# PS-VCO.net
KiCad netlist of a schematic drawn in EAGLE
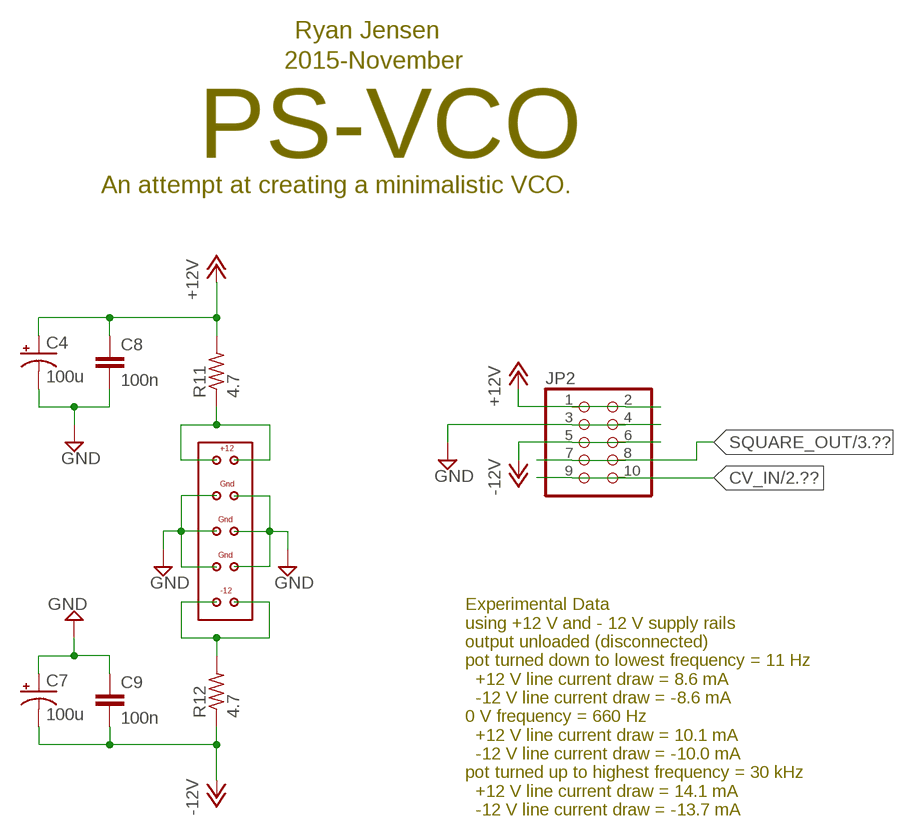
[diagram p0: schematic, sheet 1]
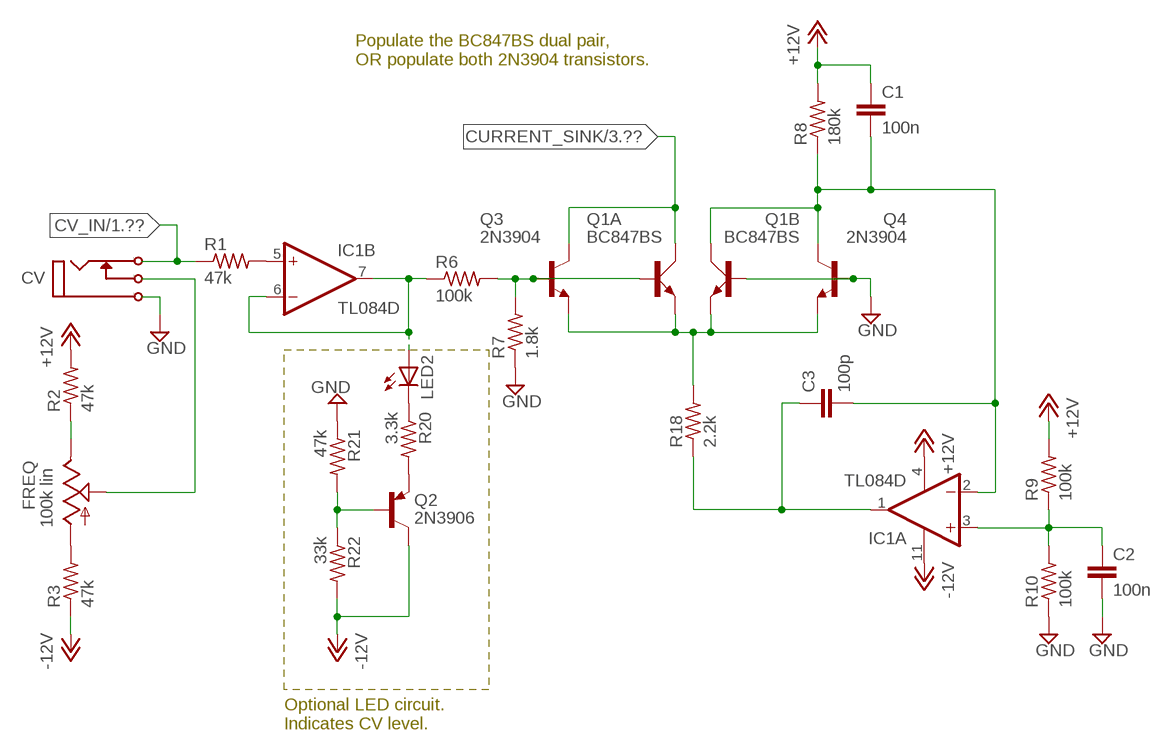
[diagram p1: schematic, sheet 2]
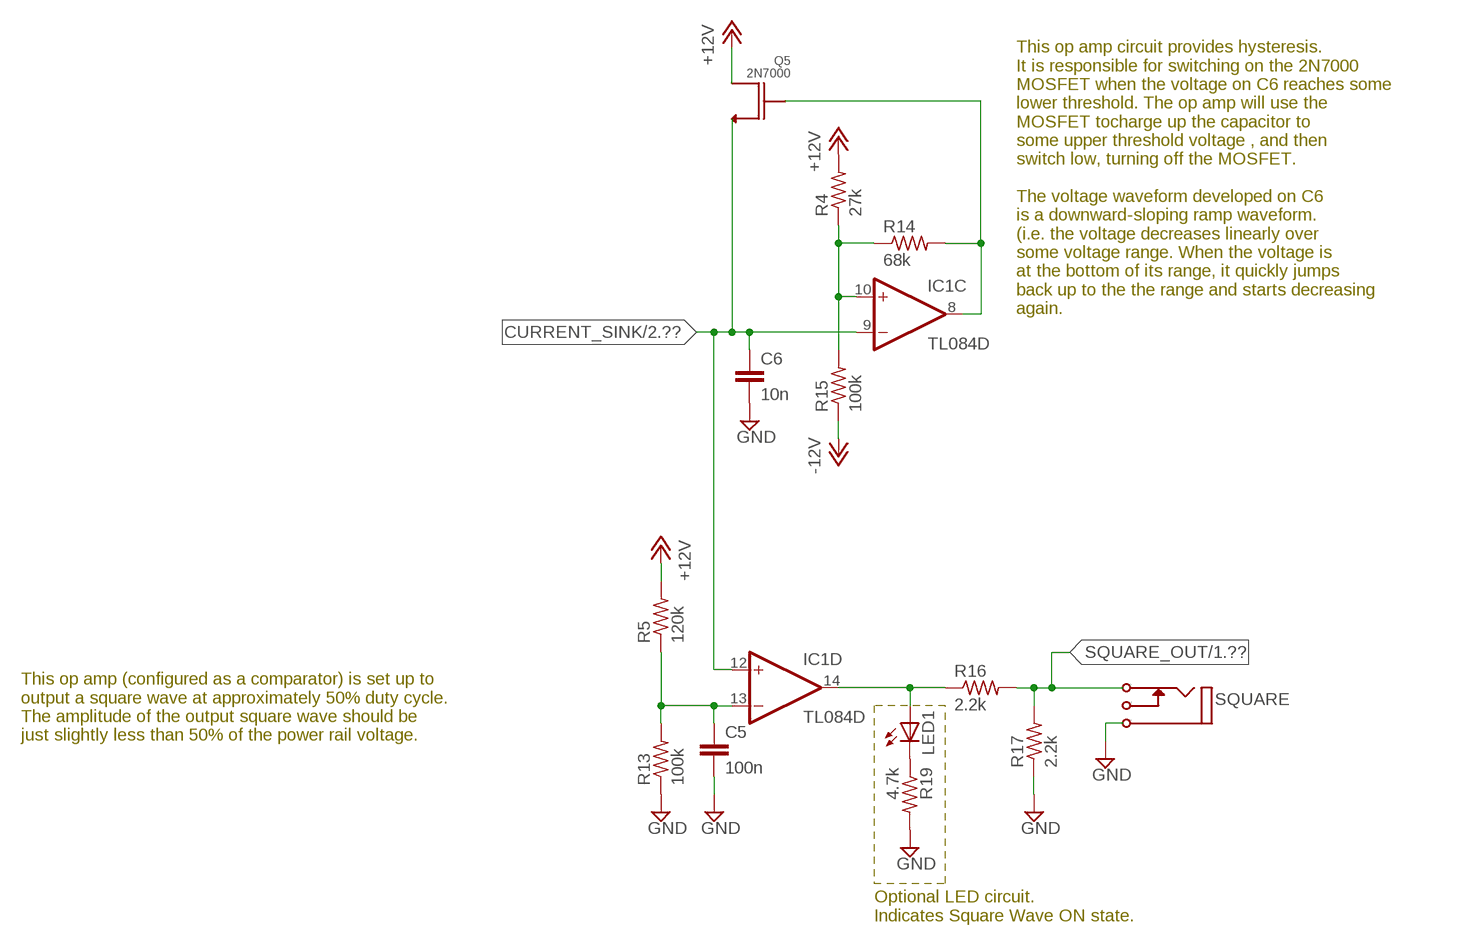
[diagram p2: schematic, sheet 3]

(export (version "E")
  (design (tool "Eeschema 10.0.6"))
  (components
    (comp (ref "C1")
      (value "100n")
      (footprint "eagle-import:C0603")
      (libsource (lib "eagle-import") (part "C-EUC0603"))
    )
    (comp (ref "C2")
      (value "100n")
      (footprint "eagle-import:C0603")
      (libsource (lib "eagle-import") (part "C-EUC0603"))
    )
    (comp (ref "C3")
      (value "100p")
      (footprint "eagle-import:C0603")
      (libsource (lib "eagle-import") (part "C-EUC0603"))
    )
    (comp (ref "CV")
      (value "CV")
      (footprint "eagle-import:MONO_JACK")
      (libsource (lib "eagle-import") (part "MONO_JACK"))
    )
    (comp (ref "FREQ")
      (value "100k lin")
      (footprint "eagle-import:B64Y")
      (libsource (lib "eagle-import") (part "TRIM_US-B64Y"))
    )
    (comp (ref "IC1")
      (value "TL084D")
      (footprint "eagle-import:SO14")
      (libsource (lib "eagle-import") (part "TL084D"))
    )
    (comp (ref "LED2")
      (value "LED_ELD260")
      (footprint "eagle-import:LED_LD260")
      (libsource (lib "eagle-import") (part "LED_ELD260"))
    )
    (comp (ref "Q1")
      (value "BC847BS")
      (footprint "eagle-import:SOT363_PHILIPS")
      (libsource (lib "eagle-import") (part "BC847BS"))
    )
    (comp (ref "Q2")
      (value "2N3906")
      (footprint "eagle-import:TO92")
      (libsource (lib "eagle-import") (part "2N3906"))
    )
    (comp (ref "Q3")
      (value "2N3904")
      (footprint "eagle-import:TO92")
      (libsource (lib "eagle-import") (part "2N3904"))
    )
    (comp (ref "Q4")
      (value "2N3904")
      (footprint "eagle-import:TO92")
      (libsource (lib "eagle-import") (part "2N3904"))
    )
    (comp (ref "R1")
      (value "47k")
      (footprint "eagle-import:R0603")
      (libsource (lib "eagle-import") (part "R-US_R0603"))
    )
    (comp (ref "R2")
      (value "47k")
      (footprint "eagle-import:R0603")
      (libsource (lib "eagle-import") (part "R-US_R0603"))
    )
    (comp (ref "R3")
      (value "47k")
      (footprint "eagle-import:R0603")
      (libsource (lib "eagle-import") (part "R-US_R0603"))
    )
    (comp (ref "R6")
      (value "100k")
      (footprint "eagle-import:R0603")
      (libsource (lib "eagle-import") (part "R-US_R0603"))
    )
    (comp (ref "R7")
      (value "1.8k")
      (footprint "eagle-import:R0603")
      (libsource (lib "eagle-import") (part "R-US_R0603"))
    )
    (comp (ref "R8")
      (value "180k")
      (footprint "eagle-import:R0603")
      (libsource (lib "eagle-import") (part "R-US_R0603"))
    )
    (comp (ref "R9")
      (value "100k")
      (footprint "eagle-import:R0603")
      (libsource (lib "eagle-import") (part "R-US_R0603"))
    )
    (comp (ref "R10")
      (value "100k")
      (footprint "eagle-import:R0603")
      (libsource (lib "eagle-import") (part "R-US_R0603"))
    )
    (comp (ref "R18")
      (value "2.2k")
      (footprint "eagle-import:R0603")
      (libsource (lib "eagle-import") (part "R-US_R0603"))
    )
    (comp (ref "R20")
      (value "3.3k")
      (footprint "eagle-import:R0603")
      (libsource (lib "eagle-import") (part "R-US_R0603"))
    )
    (comp (ref "R21")
      (value "47k")
      (footprint "eagle-import:R0603")
      (libsource (lib "eagle-import") (part "R-US_R0603"))
    )
    (comp (ref "R22")
      (value "33k")
      (footprint "eagle-import:R0603")
      (libsource (lib "eagle-import") (part "R-US_R0603"))
    )
    (comp (ref "C4")
      (value "100u")
      (footprint "eagle-import:E2,5-7")
      (libsource (lib "eagle-import") (part "CPOL-USE2.5-7"))
    )
    (comp (ref "C7")
      (value "100u")
      (footprint "eagle-import:E2,5-7")
      (libsource (lib "eagle-import") (part "CPOL-USE2.5-7"))
    )
    (comp (ref "C8")
      (value "100n")
      (footprint "eagle-import:C0603")
      (libsource (lib "eagle-import") (part "C-EUC0603"))
    )
    (comp (ref "C9")
      (value "100n")
      (footprint "eagle-import:C0603")
      (libsource (lib "eagle-import") (part "C-EUC0603"))
    )
    (comp (ref "JP2")
      (value "PINHD-2X5")
      (footprint "eagle-import:2X05")
      (libsource (lib "eagle-import") (part "PINHD-2X5"))
    )
    (comp (ref "R11")
      (value "4.7")
      (footprint "eagle-import:R0603")
      (libsource (lib "eagle-import") (part "R-US_R0603"))
    )
    (comp (ref "R12")
      (value "4.7")
      (footprint "eagle-import:R0603")
      (libsource (lib "eagle-import") (part "R-US_R0603"))
    )
    (comp (ref "U$3")
      (value "EURORACK-POWER")
      (footprint "eagle-import:EURORACK-POWER")
      (libsource (lib "eagle-import") (part "EURORACK-POWER"))
    )
    (comp (ref "C5")
      (value "100n")
      (footprint "eagle-import:C0603")
      (libsource (lib "eagle-import") (part "C-EUC0603"))
    )
    (comp (ref "C6")
      (value "10n")
      (footprint "eagle-import:C0603")
      (libsource (lib "eagle-import") (part "C-EUC0603"))
    )
    (comp (ref "LED1")
      (value "LED_ELD260")
      (footprint "eagle-import:LED_LD260")
      (libsource (lib "eagle-import") (part "LED_ELD260"))
    )
    (comp (ref "Q5")
      (value "2N7000")
      (footprint "eagle-import:2N7000")
      (libsource (lib "eagle-import") (part "2N7000"))
    )
    (comp (ref "R4")
      (value "27k")
      (footprint "eagle-import:R0603")
      (libsource (lib "eagle-import") (part "R-US_R0603"))
    )
    (comp (ref "R5")
      (value "120k")
      (footprint "eagle-import:R0603")
      (libsource (lib "eagle-import") (part "R-US_R0603"))
    )
    (comp (ref "R13")
      (value "100k")
      (footprint "eagle-import:R0603")
      (libsource (lib "eagle-import") (part "R-US_R0603"))
    )
    (comp (ref "R14")
      (value "68k")
      (footprint "eagle-import:R0603")
      (libsource (lib "eagle-import") (part "R-US_R0603"))
    )
    (comp (ref "R15")
      (value "100k")
      (footprint "eagle-import:R0603")
      (libsource (lib "eagle-import") (part "R-US_R0603"))
    )
    (comp (ref "R16")
      (value "2.2k")
      (footprint "eagle-import:R0603")
      (libsource (lib "eagle-import") (part "R-US_R0603"))
    )
    (comp (ref "R17")
      (value "2.2k")
      (footprint "eagle-import:R0603")
      (libsource (lib "eagle-import") (part "R-US_R0603"))
    )
    (comp (ref "R19")
      (value "4.7k")
      (footprint "eagle-import:R0603")
      (libsource (lib "eagle-import") (part "R-US_R0603"))
    )
    (comp (ref "SQUARE")
      (value "I/O")
      (footprint "eagle-import:MONO_JACK")
      (libsource (lib "eagle-import") (part "MONO_JACK"))
    )
  )
  (nets
    (net (code "1") (name "+12V") (class "Default")
      (node (ref "C1") (pin "1") (pinfunction "1_1") (pintype "passive"))
      (node (ref "C4") (pin "+") (pinfunction "+_+") (pintype "passive"))
      (node (ref "C8") (pin "1") (pinfunction "1_1") (pintype "passive"))
      (node (ref "IC1") (pin "4") (pinfunction "V+_4") (pintype "power_in"))
      (node (ref "JP2") (pin "1") (pinfunction "1_1") (pintype "passive"))
      (node (ref "JP2") (pin "2") (pinfunction "2_2") (pintype "passive"))
      (node (ref "Q5") (pin "D") (pinfunction "D_D") (pintype "bidirectional"))
      (node (ref "R11") (pin "2") (pinfunction "2_2") (pintype "passive"))
      (node (ref "R2") (pin "2") (pinfunction "2_2") (pintype "passive"))
      (node (ref "R4") (pin "2") (pinfunction "2_2") (pintype "passive"))
      (node (ref "R5") (pin "2") (pinfunction "2_2") (pintype "passive"))
      (node (ref "R8") (pin "2") (pinfunction "2_2") (pintype "passive"))
      (node (ref "R9") (pin "2") (pinfunction "2_2") (pintype "passive"))
    )
    (net (code "2") (name "-12V") (class "Default")
      (node (ref "C7") (pin "-") (pinfunction "-_-") (pintype "passive"))
      (node (ref "C9") (pin "2") (pinfunction "2_2") (pintype "passive"))
      (node (ref "IC1") (pin "11") (pinfunction "V-_11") (pintype "power_in"))
      (node (ref "JP2") (pin "5") (pinfunction "5_5") (pintype "passive"))
      (node (ref "JP2") (pin "6") (pinfunction "6_6") (pintype "passive"))
      (node (ref "Q2") (pin "1") (pinfunction "C_1") (pintype "passive"))
      (node (ref "R12") (pin "1") (pinfunction "1_1") (pintype "passive"))
      (node (ref "R15") (pin "1") (pinfunction "1_1") (pintype "passive"))
      (node (ref "R22") (pin "2") (pinfunction "2_2") (pintype "passive"))
      (node (ref "R3") (pin "1") (pinfunction "1_1") (pintype "passive"))
    )
    (net (code "3") (name "CURRENT_SINK") (class "Default")
      (node (ref "C6") (pin "1") (pinfunction "1_1") (pintype "passive"))
      (node (ref "IC1") (pin "12") (pinfunction "+IN_12") (pintype "input"))
      (node (ref "IC1") (pin "9") (pinfunction "-IN_9") (pintype "input"))
      (node (ref "Q1") (pin "6") (pinfunction "C_6") (pintype "passive"))
      (node (ref "Q3") (pin "1") (pinfunction "C_1") (pintype "passive"))
      (node (ref "Q5") (pin "S") (pinfunction "S_S") (pintype "bidirectional"))
    )
    (net (code "4") (name "CV_IN") (class "Default")
      (node (ref "CV") (pin "P$2") (pinfunction "P2_P$2") (pintype "bidirectional"))
      (node (ref "JP2") (pin "10") (pinfunction "10_10") (pintype "passive"))
      (node (ref "JP2") (pin "9") (pinfunction "9_9") (pintype "passive"))
      (node (ref "R1") (pin "1") (pinfunction "1_1") (pintype "passive"))
    )
    (net (code "5") (name "GND") (class "Default")
      (node (ref "C2") (pin "2") (pinfunction "2_2") (pintype "passive"))
      (node (ref "C4") (pin "-") (pinfunction "-_-") (pintype "passive"))
      (node (ref "C5") (pin "2") (pinfunction "2_2") (pintype "passive"))
      (node (ref "C6") (pin "2") (pinfunction "2_2") (pintype "passive"))
      (node (ref "C7") (pin "+") (pinfunction "+_+") (pintype "passive"))
      (node (ref "C8") (pin "2") (pinfunction "2_2") (pintype "passive"))
      (node (ref "C9") (pin "1") (pinfunction "1_1") (pintype "passive"))
      (node (ref "CV") (pin "P$1") (pinfunction "P$1_P$1") (pintype "bidirectional"))
      (node (ref "JP2") (pin "3") (pinfunction "3_3") (pintype "passive"))
      (node (ref "JP2") (pin "4") (pinfunction "4_4") (pintype "passive"))
      (node (ref "Q1") (pin "5") (pinfunction "B_5") (pintype "passive"))
      (node (ref "Q4") (pin "2") (pinfunction "B_2") (pintype "passive"))
      (node (ref "R10") (pin "1") (pinfunction "1_1") (pintype "passive"))
      (node (ref "R13") (pin "1") (pinfunction "1_1") (pintype "passive"))
      (node (ref "R17") (pin "1") (pinfunction "1_1") (pintype "passive"))
      (node (ref "R19") (pin "2") (pinfunction "2_2") (pintype "passive"))
      (node (ref "R21") (pin "1") (pinfunction "1_1") (pintype "passive"))
      (node (ref "R7") (pin "1") (pinfunction "1_1") (pintype "passive"))
      (node (ref "SQUARE") (pin "P$1") (pinfunction "P$1_P$1") (pintype "bidirectional"))
      (node (ref "U$3") (pin "P$3") (pinfunction "P$3_P$3") (pintype "bidirectional"))
      (node (ref "U$3") (pin "P$4") (pinfunction "P$4_P$4") (pintype "bidirectional"))
      (node (ref "U$3") (pin "P$5") (pinfunction "P$5_P$5") (pintype "bidirectional"))
      (node (ref "U$3") (pin "P$6") (pinfunction "P$6_P$6") (pintype "bidirectional"))
      (node (ref "U$3") (pin "P$7") (pinfunction "P$7_P$7") (pintype "bidirectional"))
      (node (ref "U$3") (pin "P$8") (pinfunction "P$8_P$8") (pintype "bidirectional"))
    )
    (net (code "6") (name "Net-(CV-P3)") (class "Default")
      (node (ref "CV") (pin "P$3") (pinfunction "P3_P$3") (pintype "bidirectional"))
      (node (ref "FREQ") (pin "S") (pinfunction "S_S") (pintype "passive"))
    )
    (net (code "7") (name "Net-(FREQ-PadA)") (class "Default")
      (node (ref "FREQ") (pin "A") (pinfunction "A_A") (pintype "passive"))
      (node (ref "R3") (pin "2") (pinfunction "2_2") (pintype "passive"))
    )
    (net (code "8") (name "Net-(FREQ-PadE)") (class "Default")
      (node (ref "FREQ") (pin "E") (pinfunction "E_E") (pintype "passive"))
      (node (ref "R2") (pin "1") (pinfunction "1_1") (pintype "passive"))
    )
    (net (code "9") (name "Net-(IC1A-+IN)") (class "Default")
      (node (ref "C2") (pin "1") (pinfunction "1_1") (pintype "passive"))
      (node (ref "IC1") (pin "3") (pinfunction "+IN_3") (pintype "input"))
      (node (ref "R10") (pin "2") (pinfunction "2_2") (pintype "passive"))
      (node (ref "R9") (pin "1") (pinfunction "1_1") (pintype "passive"))
    )
    (net (code "10") (name "Net-(IC1A--IN)") (class "Default")
      (node (ref "C1") (pin "2") (pinfunction "2_2") (pintype "passive"))
      (node (ref "C3") (pin "2") (pinfunction "2_2") (pintype "passive"))
      (node (ref "IC1") (pin "2") (pinfunction "-IN_2") (pintype "input"))
      (node (ref "Q1") (pin "3") (pinfunction "C_3") (pintype "passive"))
      (node (ref "Q4") (pin "1") (pinfunction "C_1") (pintype "passive"))
      (node (ref "R8") (pin "1") (pinfunction "1_1") (pintype "passive"))
    )
    (net (code "11") (name "Net-(IC1A-OUT)") (class "Default")
      (node (ref "C3") (pin "1") (pinfunction "1_1") (pintype "passive"))
      (node (ref "IC1") (pin "1") (pinfunction "OUT_1") (pintype "output"))
      (node (ref "R18") (pin "1") (pinfunction "1_1") (pintype "passive"))
    )
    (net (code "12") (name "Net-(IC1B-+IN)") (class "Default")
      (node (ref "IC1") (pin "5") (pinfunction "+IN_5") (pintype "input"))
      (node (ref "R1") (pin "2") (pinfunction "2_2") (pintype "passive"))
    )
    (net (code "13") (name "Net-(IC1B--IN)") (class "Default")
      (node (ref "IC1") (pin "6") (pinfunction "-IN_6") (pintype "input"))
      (node (ref "IC1") (pin "7") (pinfunction "OUT_7") (pintype "output"))
      (node (ref "LED2") (pin "A") (pinfunction "A_A") (pintype "passive"))
      (node (ref "R6") (pin "1") (pinfunction "1_1") (pintype "passive"))
    )
    (net (code "14") (name "Net-(IC1C-+IN)") (class "Default")
      (node (ref "IC1") (pin "10") (pinfunction "+IN_10") (pintype "input"))
      (node (ref "R14") (pin "1") (pinfunction "1_1") (pintype "passive"))
      (node (ref "R15") (pin "2") (pinfunction "2_2") (pintype "passive"))
      (node (ref "R4") (pin "1") (pinfunction "1_1") (pintype "passive"))
    )
    (net (code "15") (name "Net-(IC1C-OUT)") (class "Default")
      (node (ref "IC1") (pin "8") (pinfunction "OUT_8") (pintype "output"))
      (node (ref "Q5") (pin "G") (pinfunction "G_G") (pintype "bidirectional"))
      (node (ref "R14") (pin "2") (pinfunction "2_2") (pintype "passive"))
    )
    (net (code "16") (name "Net-(IC1D--IN)") (class "Default")
      (node (ref "C5") (pin "1") (pinfunction "1_1") (pintype "passive"))
      (node (ref "IC1") (pin "13") (pinfunction "-IN_13") (pintype "input"))
      (node (ref "R13") (pin "2") (pinfunction "2_2") (pintype "passive"))
      (node (ref "R5") (pin "1") (pinfunction "1_1") (pintype "passive"))
    )
    (net (code "17") (name "Net-(IC1D-OUT)") (class "Default")
      (node (ref "IC1") (pin "14") (pinfunction "OUT_14") (pintype "output"))
      (node (ref "LED1") (pin "A") (pinfunction "A_A") (pintype "passive"))
      (node (ref "R16") (pin "1") (pinfunction "1_1") (pintype "passive"))
    )
    (net (code "18") (name "Net-(LED1-C)") (class "Default")
      (node (ref "LED1") (pin "K") (pinfunction "C_K") (pintype "passive"))
      (node (ref "R19") (pin "1") (pinfunction "1_1") (pintype "passive"))
    )
    (net (code "19") (name "Net-(LED2-C)") (class "Default")
      (node (ref "LED2") (pin "K") (pinfunction "C_K") (pintype "passive"))
      (node (ref "R20") (pin "1") (pinfunction "1_1") (pintype "passive"))
    )
    (net (code "20") (name "Net-(Q1A-B)") (class "Default")
      (node (ref "Q1") (pin "2") (pinfunction "B_2") (pintype "passive"))
      (node (ref "Q3") (pin "2") (pinfunction "B_2") (pintype "passive"))
      (node (ref "R6") (pin "2") (pinfunction "2_2") (pintype "passive"))
      (node (ref "R7") (pin "2") (pinfunction "2_2") (pintype "passive"))
    )
    (net (code "21") (name "Net-(Q1A-E)") (class "Default")
      (node (ref "Q1") (pin "1") (pinfunction "E_1") (pintype "passive"))
      (node (ref "Q1") (pin "4") (pinfunction "E_4") (pintype "passive"))
      (node (ref "Q3") (pin "3") (pinfunction "E_3") (pintype "passive"))
      (node (ref "Q4") (pin "3") (pinfunction "E_3") (pintype "passive"))
      (node (ref "R18") (pin "2") (pinfunction "2_2") (pintype "passive"))
    )
    (net (code "22") (name "Net-(Q2-B)") (class "Default")
      (node (ref "Q2") (pin "2") (pinfunction "B_2") (pintype "passive"))
      (node (ref "R21") (pin "2") (pinfunction "2_2") (pintype "passive"))
      (node (ref "R22") (pin "1") (pinfunction "1_1") (pintype "passive"))
    )
    (net (code "23") (name "Net-(Q2-E)") (class "Default")
      (node (ref "Q2") (pin "3") (pinfunction "E_3") (pintype "passive"))
      (node (ref "R20") (pin "2") (pinfunction "2_2") (pintype "passive"))
    )
    (net (code "24") (name "Net-(R11-Pad1)") (class "Default")
      (node (ref "R11") (pin "1") (pinfunction "1_1") (pintype "passive"))
      (node (ref "U$3") (pin "P$1") (pinfunction "P$1_P$1") (pintype "bidirectional"))
      (node (ref "U$3") (pin "P$2") (pinfunction "P$2_P$2") (pintype "bidirectional"))
    )
    (net (code "25") (name "Net-(R12-Pad2)") (class "Default")
      (node (ref "R12") (pin "2") (pinfunction "2_2") (pintype "passive"))
      (node (ref "U$3") (pin "P$10") (pinfunction "P$10_P$10") (pintype "bidirectional"))
      (node (ref "U$3") (pin "P$9") (pinfunction "P$9_P$9") (pintype "bidirectional"))
    )
    (net (code "26") (name "SQUARE_OUT") (class "Default")
      (node (ref "JP2") (pin "7") (pinfunction "7_7") (pintype "passive"))
      (node (ref "JP2") (pin "8") (pinfunction "8_8") (pintype "passive"))
      (node (ref "R16") (pin "2") (pinfunction "2_2") (pintype "passive"))
      (node (ref "R17") (pin "2") (pinfunction "2_2") (pintype "passive"))
      (node (ref "SQUARE") (pin "P$2") (pinfunction "P2_P$2") (pintype "bidirectional"))
    )
    (net (code "27") (name "unconnected-(SQUARE-P3-PadP$3)") (class "Default")
      (node (ref "SQUARE") (pin "P$3") (pinfunction "P3_P$3") (pintype "bidirectional"))
    )
  )
)
